# Main.net
KiCad netlist of a schematic drawn in Altium Designer
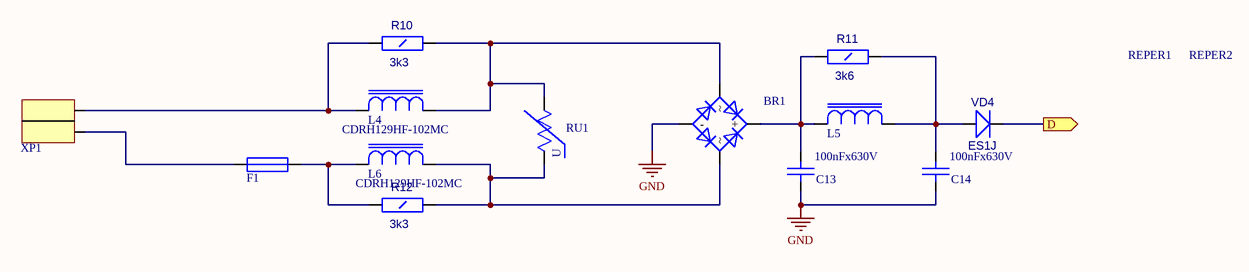
[diagram p0: Main.SchDoc]

(export (version "E")
  (design (tool "Eeschema 10.0.6"))
  (components
    (comp (ref "BR1") (value "DF10S") (footprint "SDIP") (libsource (lib "gprs_modem_2") (part "DF10S")))
    (comp (ref "C13")
      (value "100nFx630V")
      (footprint "CAP_630V_SMD")
      (libsource (lib "gprs_modem_2") (part "Cap_HV"))
    )
    (comp (ref "C14")
      (value "100nFx630V")
      (footprint "CAP_630V_SMD")
      (libsource (lib "gprs_modem_2") (part "Cap_HV"))
    )
    (comp (ref "F1")
      (value "*")
      (footprint "Fuse Belfuse")
      (libsource (lib "gprs_modem_2") (part "Fuse Belufse"))
    )
    (comp (ref "L4")
      (value "CDRH129HF-102MC")
      (footprint "IND_CDRH129")
      (libsource (lib "gprs_modem_2") (part "CDRH129"))
    )
    (comp (ref "L5")
      (value "CDRH129HF-102MC")
      (footprint "IND_CDRH129")
      (libsource (lib "gprs_modem_2") (part "CDRH129"))
    )
    (comp (ref "L6")
      (value "CDRH129HF-102MC")
      (footprint "IND_CDRH129")
      (libsource (lib "gprs_modem_2") (part "CDRH129"))
    )
    (comp (ref "R10")
      (value "3k3")
      (footprint "RC1206")
      (description "RC1206")
      (libsource (lib "gprs_modem_2") (part "RC1206"))
    )
    (comp (ref "R11")
      (value "3k6")
      (footprint "RC1206")
      (description "RC1206")
      (libsource (lib "gprs_modem_2") (part "RC1206"))
    )
    (comp (ref "R12")
      (value "3k3")
      (footprint "RC1206")
      (description "RC1206")
      (libsource (lib "gprs_modem_2") (part "RC1206"))
    )
    (comp (ref "REPER1")
      (value "REPER1.2")
      (footprint "REPER1.2")
      (libsource (lib "gprs_modem") (part "REPER1.2"))
    )
    (comp (ref "REPER2")
      (value "REPER1.2")
      (footprint "REPER1.2")
      (libsource (lib "gprs_modem") (part "REPER1.2"))
    )
    (comp (ref "RU1")
      (value "KLS6-07D")
      (footprint "Varistor_7mm_SMD")
      (libsource (lib "gprs_modem_2") (part "KLS6-07D"))
    )
    (comp (ref "VD4")
      (value "ES1J")
      (footprint "SMA")
      (description "Schottky Rectifier")
      (libsource (lib "gprs_modem_2") (part "SS14"))
    )
    (comp (ref "XP1")
      (value "*")
      (footprint "Poke-In 2pin")
      (libsource (lib "gprs_modem_2") (part "Poke-IN 2Pin"))
    )
  )
  (nets
    (net (code "1") (name "/D") (class "Default")
      (node (ref "VD4") (pin "2") (pinfunction "K_2") (pintype "passive"))
    )
    (net (code "2") (name "GND") (class "Default")
      (node (ref "BR1") (pin "4") (pinfunction "-_4") (pintype "passive"))
      (node (ref "C13") (pin "1") (pinfunction "A_1") (pintype "passive"))
      (node (ref "C14") (pin "1") (pinfunction "A_1") (pintype "passive"))
    )
    (net (code "3") (name "Net-(BR1-+)") (class "Default")
      (node (ref "BR1") (pin "3") (pinfunction "+_3") (pintype "passive"))
      (node (ref "C13") (pin "2") (pinfunction "B_2") (pintype "passive"))
      (node (ref "L5") (pin "1") (pinfunction "A_1") (pintype "passive"))
      (node (ref "R11") (pin "1") (pinfunction "A_1") (pintype "passive"))
    )
    (net (code "4") (name "Net-(C14-B)") (class "Default")
      (node (ref "C14") (pin "2") (pinfunction "B_2") (pintype "passive"))
      (node (ref "L5") (pin "2") (pinfunction "B_2") (pintype "passive"))
      (node (ref "R11") (pin "2") (pinfunction "B_2") (pintype "passive"))
      (node (ref "VD4") (pin "1") (pinfunction "A_1") (pintype "passive"))
    )
    (net (code "5") (name "Net-(L4-A)") (class "Default")
      (node (ref "L4") (pin "1") (pinfunction "A_1") (pintype "passive"))
      (node (ref "R10") (pin "1") (pinfunction "A_1") (pintype "passive"))
      (node (ref "XP1") (pin "3") (pinfunction "9_3") (pintype "passive"))
    )
    (net (code "6") (name "Net-(L4-B)") (class "Default")
      (node (ref "BR1") (pin "1") (pinfunction "~_1") (pintype "passive"))
      (node (ref "L4") (pin "2") (pinfunction "B_2") (pintype "passive"))
      (node (ref "R10") (pin "2") (pinfunction "B_2") (pintype "passive"))
      (node (ref "RU1") (pin "2") (pinfunction "B_2") (pintype "passive"))
    )
    (net (code "7") (name "Net-(L6-A)") (class "Default")
      (node (ref "F1") (pin "2") (pintype "passive"))
      (node (ref "L6") (pin "1") (pinfunction "A_1") (pintype "passive"))
      (node (ref "R12") (pin "1") (pinfunction "A_1") (pintype "passive"))
    )
    (net (code "8") (name "Net-(L6-B)") (class "Default")
      (node (ref "BR1") (pin "2") (pinfunction "~_2") (pintype "passive"))
      (node (ref "L6") (pin "2") (pinfunction "B_2") (pintype "passive"))
      (node (ref "R12") (pin "2") (pinfunction "B_2") (pintype "passive"))
      (node (ref "RU1") (pin "1") (pinfunction "A_1") (pintype "passive"))
    )
    (net (code "9") (name "Net-(XP1-10)") (class "Default")
      (node (ref "F1") (pin "1") (pintype "passive"))
      (node (ref "XP1") (pin "4") (pinfunction "10_4") (pintype "passive"))
    )
    (net (code "10") (name "unconnected-(REPER1-Pad1)") (class "Default")
      (node (ref "REPER1") (pin "1") (pintype "passive"))
    )
    (net (code "11") (name "unconnected-(REPER2-Pad1)") (class "Default")
      (node (ref "REPER2") (pin "1") (pintype "passive"))
    )
  )
)
